# MIDI_Output.net
KiCad netlist of a schematic drawn in EAGLE
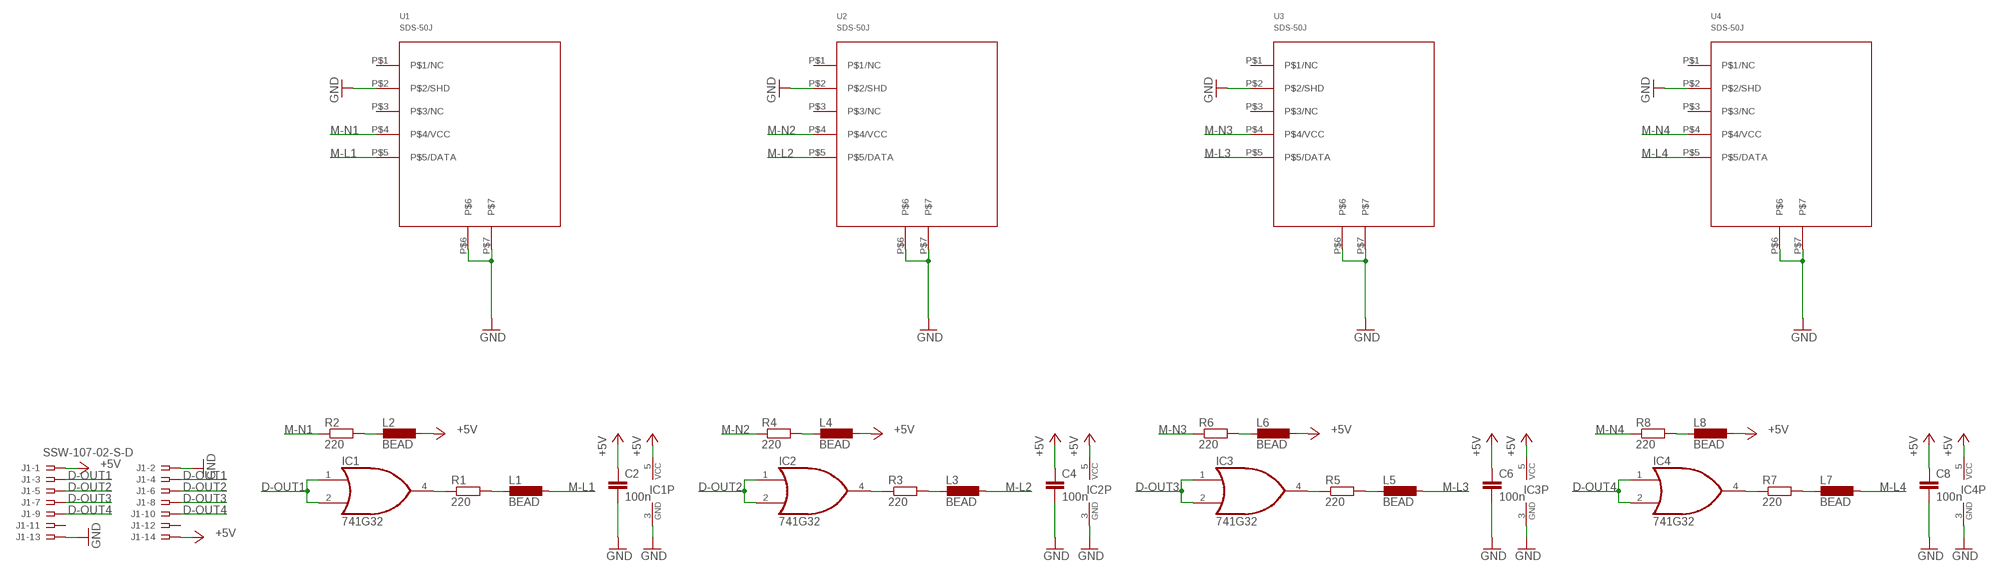
[diagram p0: schematic, sheet 1]

(export (version "E")
  (design (tool "Eeschema 10.0.6"))
  (components
    (comp (ref "C2")
      (value "100n")
      (footprint "eagle-import:C0805")
      (libsource (lib "eagle-import") (part "C-EUC0805"))
    )
    (comp (ref "C4")
      (value "100n")
      (footprint "eagle-import:C0805")
      (libsource (lib "eagle-import") (part "C-EUC0805"))
    )
    (comp (ref "C6")
      (value "100n")
      (footprint "eagle-import:C0805")
      (libsource (lib "eagle-import") (part "C-EUC0805"))
    )
    (comp (ref "C8")
      (value "100n")
      (footprint "eagle-import:C0805")
      (libsource (lib "eagle-import") (part "C-EUC0805"))
    )
    (comp (ref "IC1")
      (value "741G32")
      (footprint "eagle-import:SOT25")
      (fields (field (name "SPICEPREFIX") "J"))
      (libsource (lib "eagle-import") (part "741G32"))
    )
    (comp (ref "IC2")
      (value "741G32")
      (footprint "eagle-import:SOT25")
      (fields (field (name "SPICEPREFIX") "J"))
      (libsource (lib "eagle-import") (part "741G32"))
    )
    (comp (ref "IC3")
      (value "741G32")
      (footprint "eagle-import:SOT25")
      (fields (field (name "SPICEPREFIX") "J"))
      (libsource (lib "eagle-import") (part "741G32"))
    )
    (comp (ref "IC4")
      (value "741G32")
      (footprint "eagle-import:SOT25")
      (fields (field (name "SPICEPREFIX") "J"))
      (libsource (lib "eagle-import") (part "741G32"))
    )
    (comp (ref "J1")
      (value "SSW-107-02-S-D")
      (footprint "eagle-import:SSW-107-02-S-D")
      (libsource (lib "eagle-import") (part "SSW-107-02-S-D"))
    )
    (comp (ref "L1")
      (value "BEAD")
      (footprint "eagle-import:L0805")
      (libsource (lib "eagle-import") (part "BEAD"))
    )
    (comp (ref "L2")
      (value "BEAD")
      (footprint "eagle-import:L0805")
      (libsource (lib "eagle-import") (part "BEAD"))
    )
    (comp (ref "L3")
      (value "BEAD")
      (footprint "eagle-import:L0805")
      (libsource (lib "eagle-import") (part "BEAD"))
    )
    (comp (ref "L4")
      (value "BEAD")
      (footprint "eagle-import:L0805")
      (libsource (lib "eagle-import") (part "BEAD"))
    )
    (comp (ref "L5")
      (value "BEAD")
      (footprint "eagle-import:L0805")
      (libsource (lib "eagle-import") (part "BEAD"))
    )
    (comp (ref "L6")
      (value "BEAD")
      (footprint "eagle-import:L0805")
      (libsource (lib "eagle-import") (part "BEAD"))
    )
    (comp (ref "L7")
      (value "BEAD")
      (footprint "eagle-import:L0805")
      (libsource (lib "eagle-import") (part "BEAD"))
    )
    (comp (ref "L8")
      (value "BEAD")
      (footprint "eagle-import:L0805")
      (libsource (lib "eagle-import") (part "BEAD"))
    )
    (comp (ref "R1")
      (value "220")
      (footprint "eagle-import:R0805")
      (libsource (lib "eagle-import") (part "R-EU_R0805"))
    )
    (comp (ref "R2")
      (value "220")
      (footprint "eagle-import:R0805")
      (libsource (lib "eagle-import") (part "R-EU_R0805"))
    )
    (comp (ref "R3")
      (value "220")
      (footprint "eagle-import:R0805")
      (libsource (lib "eagle-import") (part "R-EU_R0805"))
    )
    (comp (ref "R4")
      (value "220")
      (footprint "eagle-import:R0805")
      (libsource (lib "eagle-import") (part "R-EU_R0805"))
    )
    (comp (ref "R5")
      (value "220")
      (footprint "eagle-import:R0805")
      (libsource (lib "eagle-import") (part "R-EU_R0805"))
    )
    (comp (ref "R6")
      (value "220")
      (footprint "eagle-import:R0805")
      (libsource (lib "eagle-import") (part "R-EU_R0805"))
    )
    (comp (ref "R7")
      (value "220")
      (footprint "eagle-import:R0805")
      (libsource (lib "eagle-import") (part "R-EU_R0805"))
    )
    (comp (ref "R8")
      (value "220")
      (footprint "eagle-import:R0805")
      (libsource (lib "eagle-import") (part "R-EU_R0805"))
    )
    (comp (ref "U1")
      (value "SDS-50J")
      (footprint "eagle-import:SDS-50J")
      (libsource (lib "eagle-import") (part "SDS-50J"))
    )
    (comp (ref "U2")
      (value "SDS-50J")
      (footprint "eagle-import:SDS-50J")
      (libsource (lib "eagle-import") (part "SDS-50J"))
    )
    (comp (ref "U3")
      (value "SDS-50J")
      (footprint "eagle-import:SDS-50J")
      (libsource (lib "eagle-import") (part "SDS-50J"))
    )
    (comp (ref "U4")
      (value "SDS-50J")
      (footprint "eagle-import:SDS-50J")
      (libsource (lib "eagle-import") (part "SDS-50J"))
    )
  )
  (nets
    (net (code "1") (name "+5V") (class "Default")
      (node (ref "C2") (pin "1") (pinfunction "1_1") (pintype "passive"))
      (node (ref "C4") (pin "1") (pinfunction "1_1") (pintype "passive"))
      (node (ref "C6") (pin "1") (pinfunction "1_1") (pintype "passive"))
      (node (ref "C8") (pin "1") (pinfunction "1_1") (pintype "passive"))
      (node (ref "IC1") (pin "5") (pinfunction "VCC_5") (pintype "power_in"))
      (node (ref "IC2") (pin "5") (pinfunction "VCC_5") (pintype "power_in"))
      (node (ref "IC3") (pin "5") (pinfunction "VCC_5") (pintype "power_in"))
      (node (ref "IC4") (pin "5") (pinfunction "VCC_5") (pintype "power_in"))
      (node (ref "J1") (pin "1") (pinfunction "1_1") (pintype "passive"))
      (node (ref "J1") (pin "14") (pinfunction "1_14") (pintype "passive"))
      (node (ref "L2") (pin "2") (pinfunction "2_2") (pintype "passive"))
      (node (ref "L4") (pin "2") (pinfunction "2_2") (pintype "passive"))
      (node (ref "L6") (pin "2") (pinfunction "2_2") (pintype "passive"))
      (node (ref "L8") (pin "2") (pinfunction "2_2") (pintype "passive"))
    )
    (net (code "2") (name "/D-OUT1") (class "Default")
      (node (ref "IC1") (pin "1") (pinfunction "I0_1") (pintype "input"))
      (node (ref "IC1") (pin "2") (pinfunction "I1_2") (pintype "input"))
      (node (ref "J1") (pin "3") (pinfunction "1_3") (pintype "passive"))
      (node (ref "J1") (pin "4") (pinfunction "1_4") (pintype "passive"))
    )
    (net (code "3") (name "/D-OUT2") (class "Default")
      (node (ref "IC2") (pin "1") (pinfunction "I0_1") (pintype "input"))
      (node (ref "IC2") (pin "2") (pinfunction "I1_2") (pintype "input"))
      (node (ref "J1") (pin "5") (pinfunction "1_5") (pintype "passive"))
      (node (ref "J1") (pin "6") (pinfunction "1_6") (pintype "passive"))
    )
    (net (code "4") (name "/D-OUT3") (class "Default")
      (node (ref "IC3") (pin "1") (pinfunction "I0_1") (pintype "input"))
      (node (ref "IC3") (pin "2") (pinfunction "I1_2") (pintype "input"))
      (node (ref "J1") (pin "7") (pinfunction "1_7") (pintype "passive"))
      (node (ref "J1") (pin "8") (pinfunction "1_8") (pintype "passive"))
    )
    (net (code "5") (name "/D-OUT4") (class "Default")
      (node (ref "IC4") (pin "1") (pinfunction "I0_1") (pintype "input"))
      (node (ref "IC4") (pin "2") (pinfunction "I1_2") (pintype "input"))
      (node (ref "J1") (pin "10") (pinfunction "1_10") (pintype "passive"))
      (node (ref "J1") (pin "9") (pinfunction "1_9") (pintype "passive"))
    )
    (net (code "6") (name "/M-L1") (class "Default")
      (node (ref "L1") (pin "2") (pinfunction "2_2") (pintype "passive"))
      (node (ref "U1") (pin "P$5") (pinfunction "P$5/DATA_P$5") (pintype "bidirectional"))
    )
    (net (code "7") (name "/M-L2") (class "Default")
      (node (ref "L3") (pin "2") (pinfunction "2_2") (pintype "passive"))
      (node (ref "U2") (pin "P$5") (pinfunction "P$5/DATA_P$5") (pintype "bidirectional"))
    )
    (net (code "8") (name "/M-L3") (class "Default")
      (node (ref "L5") (pin "2") (pinfunction "2_2") (pintype "passive"))
      (node (ref "U3") (pin "P$5") (pinfunction "P$5/DATA_P$5") (pintype "bidirectional"))
    )
    (net (code "9") (name "/M-L4") (class "Default")
      (node (ref "L7") (pin "2") (pinfunction "2_2") (pintype "passive"))
      (node (ref "U4") (pin "P$5") (pinfunction "P$5/DATA_P$5") (pintype "bidirectional"))
    )
    (net (code "10") (name "/M-N1") (class "Default")
      (node (ref "R2") (pin "1") (pinfunction "1_1") (pintype "passive"))
      (node (ref "U1") (pin "P$4") (pinfunction "P$4/VCC_P$4") (pintype "bidirectional"))
    )
    (net (code "11") (name "/M-N2") (class "Default")
      (node (ref "R4") (pin "1") (pinfunction "1_1") (pintype "passive"))
      (node (ref "U2") (pin "P$4") (pinfunction "P$4/VCC_P$4") (pintype "bidirectional"))
    )
    (net (code "12") (name "/M-N3") (class "Default")
      (node (ref "R6") (pin "1") (pinfunction "1_1") (pintype "passive"))
      (node (ref "U3") (pin "P$4") (pinfunction "P$4/VCC_P$4") (pintype "bidirectional"))
    )
    (net (code "13") (name "/M-N4") (class "Default")
      (node (ref "R8") (pin "1") (pinfunction "1_1") (pintype "passive"))
      (node (ref "U4") (pin "P$4") (pinfunction "P$4/VCC_P$4") (pintype "bidirectional"))
    )
    (net (code "14") (name "GND") (class "Default")
      (node (ref "C2") (pin "2") (pinfunction "2_2") (pintype "passive"))
      (node (ref "C4") (pin "2") (pinfunction "2_2") (pintype "passive"))
      (node (ref "C6") (pin "2") (pinfunction "2_2") (pintype "passive"))
      (node (ref "C8") (pin "2") (pinfunction "2_2") (pintype "passive"))
      (node (ref "IC1") (pin "3") (pinfunction "GND_3") (pintype "power_in"))
      (node (ref "IC2") (pin "3") (pinfunction "GND_3") (pintype "power_in"))
      (node (ref "IC3") (pin "3") (pinfunction "GND_3") (pintype "power_in"))
      (node (ref "IC4") (pin "3") (pinfunction "GND_3") (pintype "power_in"))
      (node (ref "J1") (pin "13") (pinfunction "1_13") (pintype "passive"))
      (node (ref "J1") (pin "2") (pinfunction "1_2") (pintype "passive"))
      (node (ref "U1") (pin "P$2") (pinfunction "P$2/SHD_P$2") (pintype "bidirectional"))
      (node (ref "U1") (pin "P$6") (pinfunction "P$6_P$6") (pintype "bidirectional"))
      (node (ref "U1") (pin "P$7") (pinfunction "P$7_P$7") (pintype "bidirectional"))
      (node (ref "U2") (pin "P$2") (pinfunction "P$2/SHD_P$2") (pintype "bidirectional"))
      (node (ref "U2") (pin "P$6") (pinfunction "P$6_P$6") (pintype "bidirectional"))
      (node (ref "U2") (pin "P$7") (pinfunction "P$7_P$7") (pintype "bidirectional"))
      (node (ref "U3") (pin "P$2") (pinfunction "P$2/SHD_P$2") (pintype "bidirectional"))
      (node (ref "U3") (pin "P$6") (pinfunction "P$6_P$6") (pintype "bidirectional"))
      (node (ref "U3") (pin "P$7") (pinfunction "P$7_P$7") (pintype "bidirectional"))
      (node (ref "U4") (pin "P$2") (pinfunction "P$2/SHD_P$2") (pintype "bidirectional"))
      (node (ref "U4") (pin "P$6") (pinfunction "P$6_P$6") (pintype "bidirectional"))
      (node (ref "U4") (pin "P$7") (pinfunction "P$7_P$7") (pintype "bidirectional"))
    )
    (net (code "15") (name "Net-(IC1A-O)") (class "Default")
      (node (ref "IC1") (pin "4") (pinfunction "O_4") (pintype "output"))
      (node (ref "R1") (pin "1") (pinfunction "1_1") (pintype "passive"))
    )
    (net (code "16") (name "Net-(IC2A-O)") (class "Default")
      (node (ref "IC2") (pin "4") (pinfunction "O_4") (pintype "output"))
      (node (ref "R3") (pin "1") (pinfunction "1_1") (pintype "passive"))
    )
    (net (code "17") (name "Net-(IC3A-O)") (class "Default")
      (node (ref "IC3") (pin "4") (pinfunction "O_4") (pintype "output"))
      (node (ref "R5") (pin "1") (pinfunction "1_1") (pintype "passive"))
    )
    (net (code "18") (name "Net-(IC4A-O)") (class "Default")
      (node (ref "IC4") (pin "4") (pinfunction "O_4") (pintype "output"))
      (node (ref "R7") (pin "1") (pinfunction "1_1") (pintype "passive"))
    )
    (net (code "19") (name "Net-(L1-Pad1)") (class "Default")
      (node (ref "L1") (pin "1") (pinfunction "1_1") (pintype "passive"))
      (node (ref "R1") (pin "2") (pinfunction "2_2") (pintype "passive"))
    )
    (net (code "20") (name "Net-(L2-Pad1)") (class "Default")
      (node (ref "L2") (pin "1") (pinfunction "1_1") (pintype "passive"))
      (node (ref "R2") (pin "2") (pinfunction "2_2") (pintype "passive"))
    )
    (net (code "21") (name "Net-(L3-Pad1)") (class "Default")
      (node (ref "L3") (pin "1") (pinfunction "1_1") (pintype "passive"))
      (node (ref "R3") (pin "2") (pinfunction "2_2") (pintype "passive"))
    )
    (net (code "22") (name "Net-(L4-Pad1)") (class "Default")
      (node (ref "L4") (pin "1") (pinfunction "1_1") (pintype "passive"))
      (node (ref "R4") (pin "2") (pinfunction "2_2") (pintype "passive"))
    )
    (net (code "23") (name "Net-(L5-Pad1)") (class "Default")
      (node (ref "L5") (pin "1") (pinfunction "1_1") (pintype "passive"))
      (node (ref "R5") (pin "2") (pinfunction "2_2") (pintype "passive"))
    )
    (net (code "24") (name "Net-(L6-Pad1)") (class "Default")
      (node (ref "L6") (pin "1") (pinfunction "1_1") (pintype "passive"))
      (node (ref "R6") (pin "2") (pinfunction "2_2") (pintype "passive"))
    )
    (net (code "25") (name "Net-(L7-Pad1)") (class "Default")
      (node (ref "L7") (pin "1") (pinfunction "1_1") (pintype "passive"))
      (node (ref "R7") (pin "2") (pinfunction "2_2") (pintype "passive"))
    )
    (net (code "26") (name "Net-(L8-Pad1)") (class "Default")
      (node (ref "L8") (pin "1") (pinfunction "1_1") (pintype "passive"))
      (node (ref "R8") (pin "2") (pinfunction "2_2") (pintype "passive"))
    )
    (net (code "27") (name "unconnected-(J1C-1-Pad11)") (class "Default")
      (node (ref "J1") (pin "11") (pinfunction "1_11") (pintype "passive"))
    )
    (net (code "28") (name "unconnected-(J1D-1-Pad12)") (class "Default")
      (node (ref "J1") (pin "12") (pinfunction "1_12") (pintype "passive"))
    )
    (net (code "29") (name "unconnected-(U1-P$1{slash}NC-PadP$1)") (class "Default")
      (node (ref "U1") (pin "P$1") (pinfunction "P$1/NC_P$1") (pintype "bidirectional"))
    )
    (net (code "30") (name "unconnected-(U1-P$3{slash}NC-PadP$3)") (class "Default")
      (node (ref "U1") (pin "P$3") (pinfunction "P$3/NC_P$3") (pintype "bidirectional"))
    )
    (net (code "31") (name "unconnected-(U2-P$1{slash}NC-PadP$1)") (class "Default")
      (node (ref "U2") (pin "P$1") (pinfunction "P$1/NC_P$1") (pintype "bidirectional"))
    )
    (net (code "32") (name "unconnected-(U2-P$3{slash}NC-PadP$3)") (class "Default")
      (node (ref "U2") (pin "P$3") (pinfunction "P$3/NC_P$3") (pintype "bidirectional"))
    )
    (net (code "33") (name "unconnected-(U3-P$1{slash}NC-PadP$1)") (class "Default")
      (node (ref "U3") (pin "P$1") (pinfunction "P$1/NC_P$1") (pintype "bidirectional"))
    )
    (net (code "34") (name "unconnected-(U3-P$3{slash}NC-PadP$3)") (class "Default")
      (node (ref "U3") (pin "P$3") (pinfunction "P$3/NC_P$3") (pintype "bidirectional"))
    )
    (net (code "35") (name "unconnected-(U4-P$1{slash}NC-PadP$1)") (class "Default")
      (node (ref "U4") (pin "P$1") (pinfunction "P$1/NC_P$1") (pintype "bidirectional"))
    )
    (net (code "36") (name "unconnected-(U4-P$3{slash}NC-PadP$3)") (class "Default")
      (node (ref "U4") (pin "P$3") (pinfunction "P$3/NC_P$3") (pintype "bidirectional"))
    )
  )
)
